# Bin_C_Box.net
KiCad netlist of a schematic drawn in Altium Designer
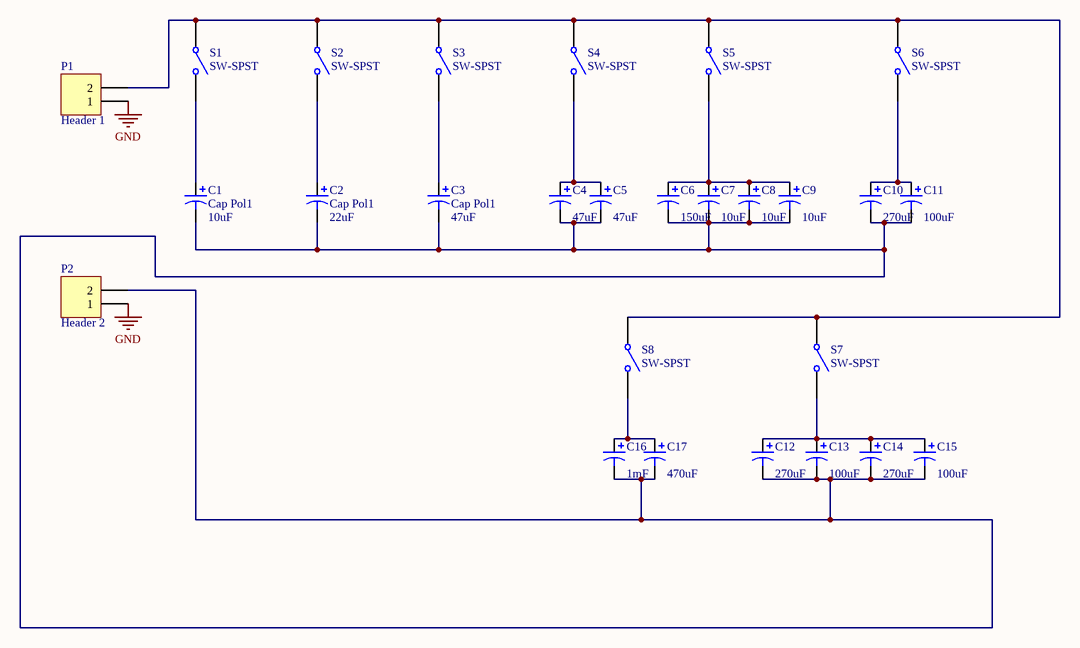
[diagram p0: Bin_C_Box.SchDoc]

(export (version "E")
  (design (tool "Eeschema 10.0.6"))
  (components
    (comp (ref "C1")
      (value "Cap Pol1")
      (footprint "CAP_2_5")
      (description "Polarized Capacitor (Radial)")
      (fields (field (name "ALTIUM_VALUE") "10uF") (field (name "PUBLISHER") "Altium Limited"))
      (libsource (lib "Miscellaneous Devices") (part "Cap Pol1"))
    )
    (comp (ref "C2")
      (value "Cap Pol1")
      (footprint "CAP_2_5")
      (description "Polarized Capacitor (Radial)")
      (fields (field (name "ALTIUM_VALUE") "22uF") (field (name "PUBLISHER") "Altium Limited"))
      (libsource (lib "Miscellaneous Devices") (part "Cap Pol1"))
    )
    (comp (ref "C3")
      (value "Cap Pol1")
      (footprint "CAP_3_8")
      (description "Polarized Capacitor (Radial)")
      (fields (field (name "ALTIUM_VALUE") "47uF") (field (name "PUBLISHER") "Altium Limited"))
      (libsource (lib "Miscellaneous Devices") (part "Cap Pol1"))
    )
    (comp (ref "C4")
      (value "47uF")
      (footprint "CAP_3_8")
      (description "Polarized Capacitor (Radial)")
      (fields (field (name "Comment") "Cap Pol1") (field (name "PUBLISHER") "Altium Limited"))
      (libsource (lib "Miscellaneous Devices") (part "Cap Pol1"))
    )
    (comp (ref "C5")
      (value "47uF")
      (footprint "CAP_3_8")
      (description "Polarized Capacitor (Radial)")
      (fields (field (name "PUBLISHER") "Altium Limited"))
      (libsource (lib "Miscellaneous Devices") (part "Cap Pol1"))
    )
    (comp (ref "C6")
      (value "150uF")
      (footprint "CAP_5_13")
      (description "Polarized Capacitor (Radial)")
      (fields (field (name "PUBLISHER") "Altium Limited"))
      (libsource (lib "Miscellaneous Devices") (part "Cap Pol1"))
    )
    (comp (ref "C7")
      (value "10uF")
      (footprint "CAP_2_5")
      (description "Polarized Capacitor (Radial)")
      (fields (field (name "PUBLISHER") "Altium Limited"))
      (libsource (lib "Miscellaneous Devices") (part "Cap Pol1"))
    )
    (comp (ref "C8")
      (value "10uF")
      (footprint "CAP_2_5")
      (description "Polarized Capacitor (Radial)")
      (fields (field (name "Comment") "Cap Pol1") (field (name "PUBLISHER") "Altium Limited"))
      (libsource (lib "Miscellaneous Devices") (part "Cap Pol1"))
    )
    (comp (ref "C9")
      (value "10uF")
      (footprint "CAP_2_5")
      (description "Polarized Capacitor (Radial)")
      (fields (field (name "PUBLISHER") "Altium Limited"))
      (libsource (lib "Miscellaneous Devices") (part "Cap Pol1"))
    )
    (comp (ref "C10")
      (value "270uF")
      (footprint "CAP_5_13")
      (description "Polarized Capacitor (Radial)")
      (fields (field (name "Comment") "Cap Pol1") (field (name "PUBLISHER") "Altium Limited"))
      (libsource (lib "Miscellaneous Devices") (part "Cap Pol1"))
    )
    (comp (ref "C11")
      (value "100uF")
      (footprint "CAP_3_8")
      (description "Polarized Capacitor (Radial)")
      (fields (field (name "Comment") "Cap Pol1") (field (name "PUBLISHER") "Altium Limited"))
      (libsource (lib "Miscellaneous Devices") (part "Cap Pol1"))
    )
    (comp (ref "C12")
      (value "270uF")
      (footprint "CAP_5_13")
      (description "Polarized Capacitor (Radial)")
      (fields (field (name "Comment") "Cap Pol1") (field (name "PUBLISHER") "Altium Limited"))
      (libsource (lib "Miscellaneous Devices") (part "Cap Pol1"))
    )
    (comp (ref "C13")
      (value "100uF")
      (footprint "CAP_3_8")
      (description "Polarized Capacitor (Radial)")
      (fields (field (name "Comment") "Cap Pol1") (field (name "PUBLISHER") "Altium Limited"))
      (libsource (lib "Miscellaneous Devices") (part "Cap Pol1"))
    )
    (comp (ref "C14")
      (value "270uF")
      (footprint "CAP_5_13")
      (description "Polarized Capacitor (Radial)")
      (fields (field (name "Comment") "Cap Pol1") (field (name "PUBLISHER") "Altium Limited"))
      (libsource (lib "Miscellaneous Devices") (part "Cap Pol1"))
    )
    (comp (ref "C15")
      (value "100uF")
      (footprint "CAP_3_8")
      (description "Polarized Capacitor (Radial)")
      (fields (field (name "Comment") "Cap Pol1") (field (name "PUBLISHER") "Altium Limited"))
      (libsource (lib "Miscellaneous Devices") (part "Cap Pol1"))
    )
    (comp (ref "C16")
      (value "1mF")
      (footprint "CAP_5_13")
      (description "Polarized Capacitor (Radial)")
      (fields (field (name "Comment") "Cap Pol1") (field (name "PUBLISHER") "Altium Limited"))
      (libsource (lib "Miscellaneous Devices") (part "Cap Pol1"))
    )
    (comp (ref "C17")
      (value "470uF")
      (footprint "CAP_5_13")
      (description "Polarized Capacitor (Radial)")
      (fields (field (name "Comment") "Cap Pol1") (field (name "PUBLISHER") "Altium Limited"))
      (libsource (lib "Miscellaneous Devices") (part "Cap Pol1"))
    )
    (comp (ref "P1")
      (value "Header 1")
      (footprint "Header Block")
      (description "Header, 2-Pin")
      (fields (field (name "PUBLISHER") "Altium Limited"))
      (libsource (lib "Miscellaneous Connectors") (part "Header 2"))
    )
    (comp (ref "P2")
      (value "Header 2")
      (footprint "Header Block")
      (description "Header, 2-Pin")
      (fields (field (name "PUBLISHER") "Altium Limited"))
      (libsource (lib "Miscellaneous Connectors") (part "Header 2"))
    )
    (comp (ref "S1")
      (value "SW-SPST")
      (footprint "SPST")
      (description "Single-Pole, Single-Throw Switch")
      (fields (field (name "PUBLISHER") "Altium Limited"))
      (libsource (lib "Miscellaneous Devices") (part "SW-SPST"))
    )
    (comp (ref "S2")
      (value "SW-SPST")
      (footprint "SPST")
      (description "Single-Pole, Single-Throw Switch")
      (fields (field (name "PUBLISHER") "Altium Limited"))
      (libsource (lib "Miscellaneous Devices") (part "SW-SPST"))
    )
    (comp (ref "S3")
      (value "SW-SPST")
      (footprint "SPST")
      (description "Single-Pole, Single-Throw Switch")
      (fields (field (name "PUBLISHER") "Altium Limited"))
      (libsource (lib "Miscellaneous Devices") (part "SW-SPST"))
    )
    (comp (ref "S4")
      (value "SW-SPST")
      (footprint "SPST")
      (description "Single-Pole, Single-Throw Switch")
      (fields (field (name "PUBLISHER") "Altium Limited"))
      (libsource (lib "Miscellaneous Devices") (part "SW-SPST"))
    )
    (comp (ref "S5")
      (value "SW-SPST")
      (footprint "SPST")
      (description "Single-Pole, Single-Throw Switch")
      (fields (field (name "PUBLISHER") "Altium Limited"))
      (libsource (lib "Miscellaneous Devices") (part "SW-SPST"))
    )
    (comp (ref "S6")
      (value "SW-SPST")
      (footprint "SPST")
      (description "Single-Pole, Single-Throw Switch")
      (fields (field (name "PUBLISHER") "Altium Limited"))
      (libsource (lib "Miscellaneous Devices") (part "SW-SPST"))
    )
    (comp (ref "S7")
      (value "SW-SPST")
      (footprint "SPST")
      (description "Single-Pole, Single-Throw Switch")
      (fields (field (name "PUBLISHER") "Altium Limited"))
      (libsource (lib "Miscellaneous Devices") (part "SW-SPST"))
    )
    (comp (ref "S8")
      (value "SW-SPST")
      (footprint "SPST")
      (description "Single-Pole, Single-Throw Switch")
      (fields (field (name "PUBLISHER") "Altium Limited"))
      (libsource (lib "Miscellaneous Devices") (part "SW-SPST"))
    )
  )
  (nets
    (net (code "1") (name "GND") (class "Default")
      (node (ref "P1") (pin "1") (pinfunction "1_1") (pintype "passive"))
      (node (ref "P2") (pin "1") (pinfunction "1_1") (pintype "passive"))
    )
    (net (code "2") (name "Net-(C1-Pad2)") (class "Default")
      (node (ref "C1") (pin "2") (pinfunction "2_2") (pintype "passive"))
      (node (ref "C10") (pin "2") (pinfunction "2_2") (pintype "passive"))
      (node (ref "C11") (pin "2") (pinfunction "2_2") (pintype "passive"))
      (node (ref "C12") (pin "2") (pinfunction "2_2") (pintype "passive"))
      (node (ref "C13") (pin "2") (pinfunction "2_2") (pintype "passive"))
      (node (ref "C14") (pin "2") (pinfunction "2_2") (pintype "passive"))
      (node (ref "C15") (pin "2") (pinfunction "2_2") (pintype "passive"))
      (node (ref "C16") (pin "2") (pinfunction "2_2") (pintype "passive"))
      (node (ref "C17") (pin "2") (pinfunction "2_2") (pintype "passive"))
      (node (ref "C2") (pin "2") (pinfunction "2_2") (pintype "passive"))
      (node (ref "C3") (pin "2") (pinfunction "2_2") (pintype "passive"))
      (node (ref "C4") (pin "2") (pinfunction "2_2") (pintype "passive"))
      (node (ref "C5") (pin "2") (pinfunction "2_2") (pintype "passive"))
      (node (ref "C6") (pin "2") (pinfunction "2_2") (pintype "passive"))
      (node (ref "C7") (pin "2") (pinfunction "2_2") (pintype "passive"))
      (node (ref "C8") (pin "2") (pinfunction "2_2") (pintype "passive"))
      (node (ref "C9") (pin "2") (pinfunction "2_2") (pintype "passive"))
      (node (ref "P2") (pin "2") (pinfunction "2_2") (pintype "passive"))
    )
    (net (code "3") (name "Net-(S1-COMMON)") (class "Default")
      (node (ref "P1") (pin "2") (pinfunction "2_2") (pintype "passive"))
      (node (ref "S1") (pin "1") (pinfunction "COMMON_1") (pintype "passive"))
      (node (ref "S2") (pin "1") (pinfunction "COMMON_1") (pintype "passive"))
      (node (ref "S3") (pin "1") (pinfunction "COMMON_1") (pintype "passive"))
      (node (ref "S4") (pin "1") (pinfunction "COMMON_1") (pintype "passive"))
      (node (ref "S5") (pin "1") (pinfunction "COMMON_1") (pintype "passive"))
      (node (ref "S6") (pin "1") (pinfunction "COMMON_1") (pintype "passive"))
      (node (ref "S7") (pin "1") (pinfunction "COMMON_1") (pintype "passive"))
      (node (ref "S8") (pin "1") (pinfunction "COMMON_1") (pintype "passive"))
    )
    (net (code "4") (name "Net-(S1-NO)") (class "Default")
      (node (ref "C1") (pin "1") (pinfunction "1_1") (pintype "passive"))
      (node (ref "S1") (pin "2") (pinfunction "NO_2") (pintype "passive"))
    )
    (net (code "5") (name "Net-(S2-NO)") (class "Default")
      (node (ref "C2") (pin "1") (pinfunction "1_1") (pintype "passive"))
      (node (ref "S2") (pin "2") (pinfunction "NO_2") (pintype "passive"))
    )
    (net (code "6") (name "Net-(S3-NO)") (class "Default")
      (node (ref "C3") (pin "1") (pinfunction "1_1") (pintype "passive"))
      (node (ref "S3") (pin "2") (pinfunction "NO_2") (pintype "passive"))
    )
    (net (code "7") (name "Net-(S4-NO)") (class "Default")
      (node (ref "C4") (pin "1") (pinfunction "1_1") (pintype "passive"))
      (node (ref "C5") (pin "1") (pinfunction "1_1") (pintype "passive"))
      (node (ref "S4") (pin "2") (pinfunction "NO_2") (pintype "passive"))
    )
    (net (code "8") (name "Net-(S5-NO)") (class "Default")
      (node (ref "C6") (pin "1") (pinfunction "1_1") (pintype "passive"))
      (node (ref "C7") (pin "1") (pinfunction "1_1") (pintype "passive"))
      (node (ref "C8") (pin "1") (pinfunction "1_1") (pintype "passive"))
      (node (ref "C9") (pin "1") (pinfunction "1_1") (pintype "passive"))
      (node (ref "S5") (pin "2") (pinfunction "NO_2") (pintype "passive"))
    )
    (net (code "9") (name "Net-(S6-NO)") (class "Default")
      (node (ref "C10") (pin "1") (pinfunction "1_1") (pintype "passive"))
      (node (ref "C11") (pin "1") (pinfunction "1_1") (pintype "passive"))
      (node (ref "S6") (pin "2") (pinfunction "NO_2") (pintype "passive"))
    )
    (net (code "10") (name "Net-(S7-NO)") (class "Default")
      (node (ref "C12") (pin "1") (pinfunction "1_1") (pintype "passive"))
      (node (ref "C13") (pin "1") (pinfunction "1_1") (pintype "passive"))
      (node (ref "C14") (pin "1") (pinfunction "1_1") (pintype "passive"))
      (node (ref "C15") (pin "1") (pinfunction "1_1") (pintype "passive"))
      (node (ref "S7") (pin "2") (pinfunction "NO_2") (pintype "passive"))
    )
    (net (code "11") (name "Net-(S8-NO)") (class "Default")
      (node (ref "C16") (pin "1") (pinfunction "1_1") (pintype "passive"))
      (node (ref "C17") (pin "1") (pinfunction "1_1") (pintype "passive"))
      (node (ref "S8") (pin "2") (pinfunction "NO_2") (pintype "passive"))
    )
  )
)
